# Interfaces.net
KiCad netlist of a schematic drawn in Altium Designer
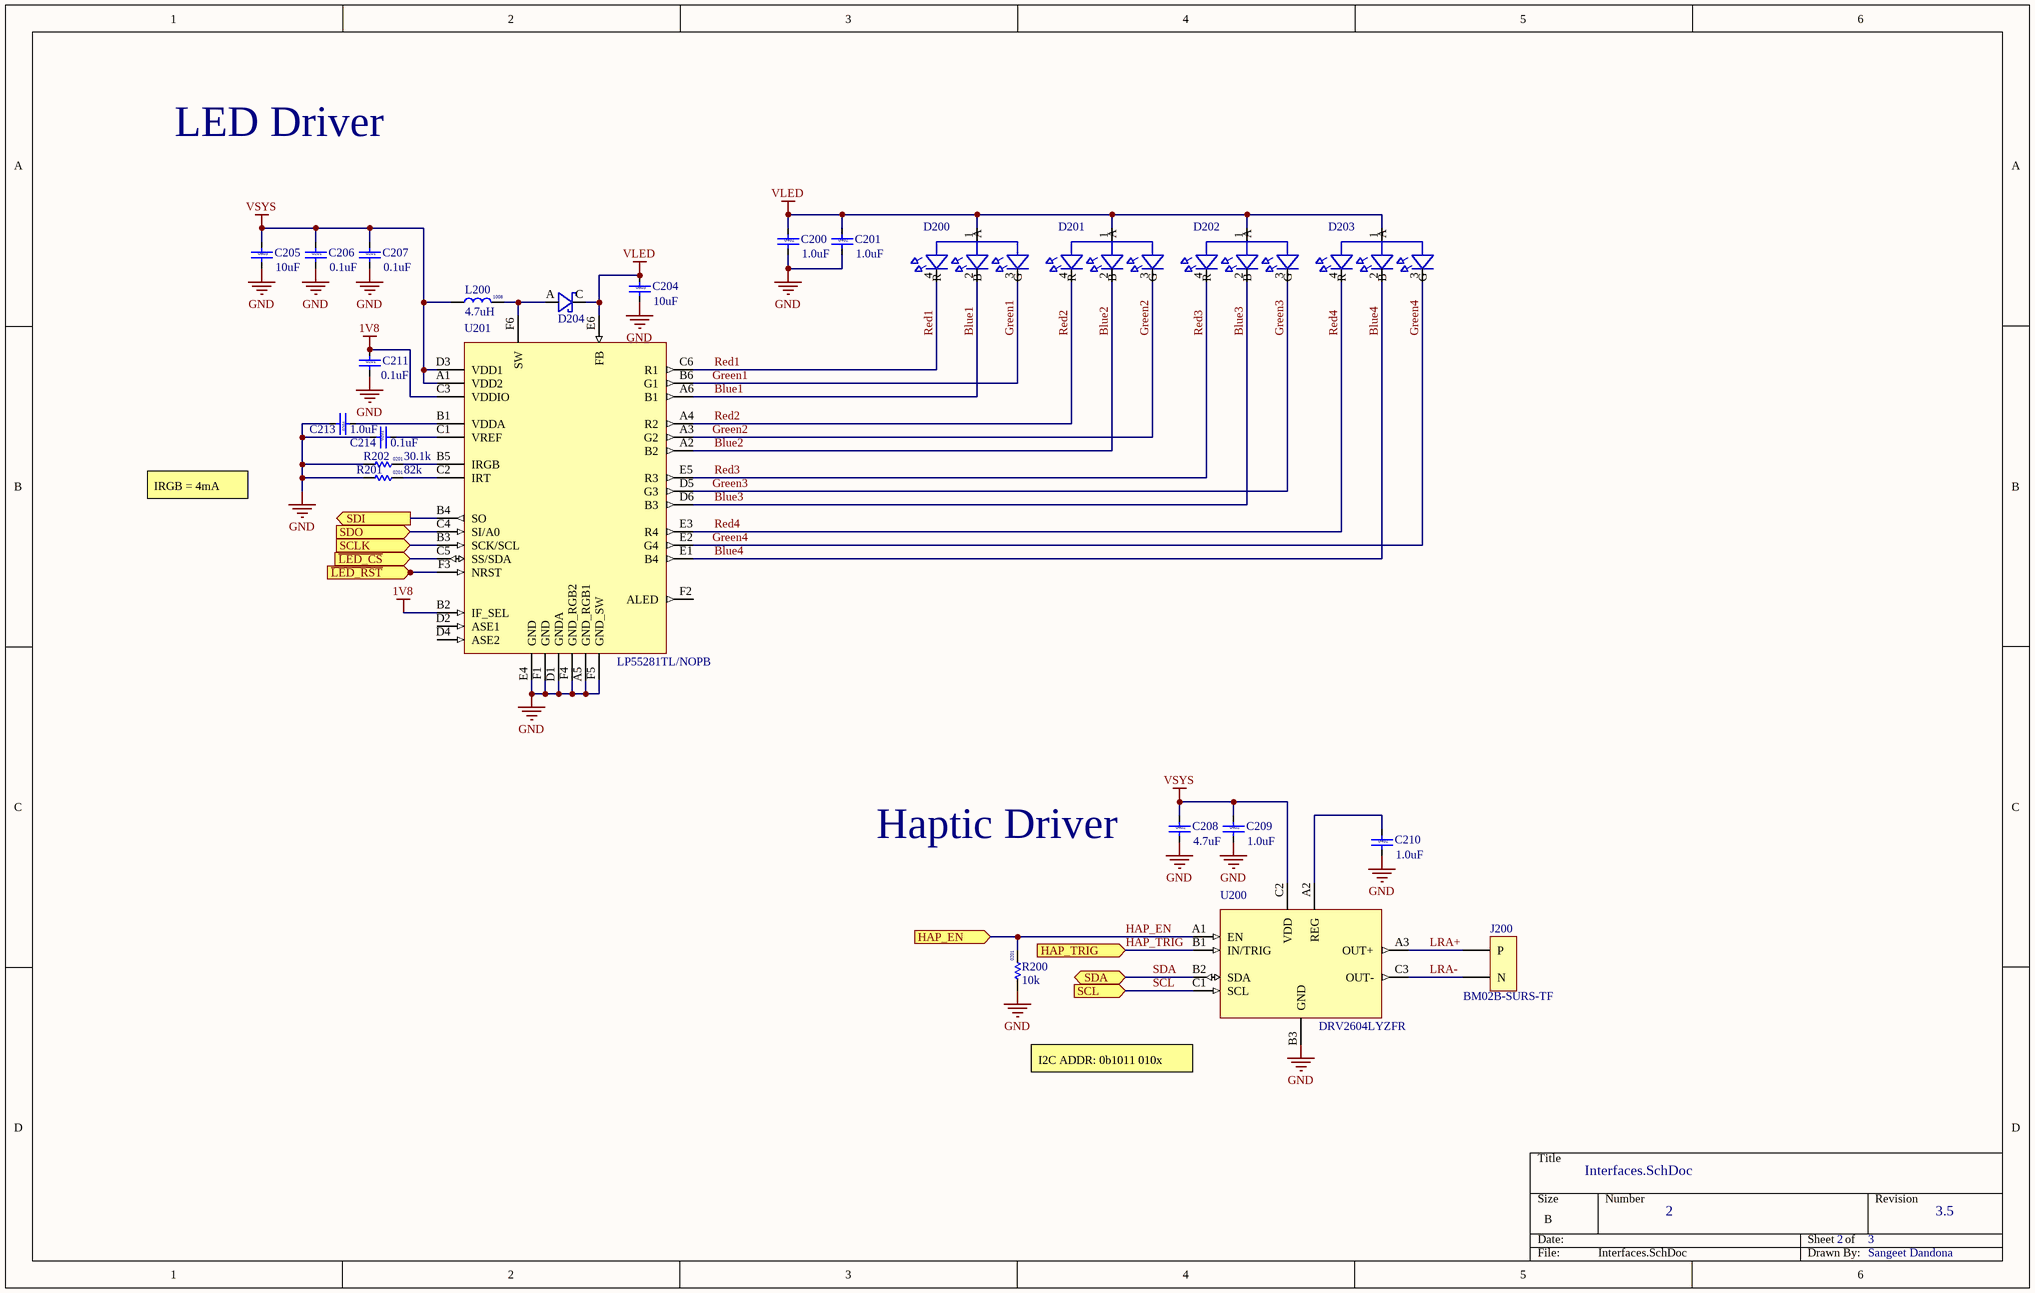
[diagram p0: Interfaces.SchDoc]

(export (version "E")
  (design (tool "Eeschema 10.0.6"))
  (components
    (comp (ref "C200")
      (value "1.0uF")
      (footprint "Cap 0402 HD")
      (description "CAP CER 1UF 10V 10% X5R 0402")
      (fields (field (name "SIZE") "0402") (field (name "MF") "Murata Electronics North America"))
      (libsource (lib "Rigado_AltiumLib") (part "Cap Chip"))
    )
    (comp (ref "C201")
      (value "1.0uF")
      (footprint "Cap 0402 HD")
      (description "CAP CER 1UF 10V 10% X5R 0402")
      (fields (field (name "SIZE") "0402") (field (name "MF") "Murata Electronics North America"))
      (libsource (lib "Rigado_AltiumLib") (part "Cap Chip"))
    )
    (comp (ref "C204")
      (value "10uF")
      (footprint "Cap 0603")
      (description "CAP CER 10UF 10V 20% X5R 0603")
      (fields (field (name "SIZE") "0603") (field (name "MF") "TDK Corporation"))
      (libsource (lib "Rigado_AltiumLib") (part "Cap Chip"))
    )
    (comp (ref "C205")
      (value "10uF")
      (footprint "Cap 0603")
      (description "CAP CER 10UF 10V 20% X5R 0603")
      (fields (field (name "SIZE") "0603") (field (name "MF") "TDK Corporation"))
      (libsource (lib "Rigado_AltiumLib") (part "Cap Chip"))
    )
    (comp (ref "C206")
      (value "0.1uF")
      (footprint "Cap 0201 HD")
      (description "CAP CER 0.1UF 6.3V 10% X5R 0201")
      (fields (field (name "SIZE") "0201") (field (name "MF") "Murata Electronics North America"))
      (libsource (lib "Rigado_AltiumLib") (part "Cap Chip"))
    )
    (comp (ref "C207")
      (value "0.1uF")
      (footprint "Cap 0201 HD")
      (description "CAP CER 0.1UF 6.3V 10% X5R 0201")
      (fields (field (name "SIZE") "0201") (field (name "MF") "Murata Electronics North America"))
      (libsource (lib "Rigado_AltiumLib") (part "Cap Chip"))
    )
    (comp (ref "C208")
      (value "4.7uF")
      (footprint "Cap 0402 HD")
      (description "CAP CER 4.7UF 10V 20% X5R 0402")
      (fields (field (name "SIZE") "0402") (field (name "MF") "Samsung Electro-Mechanics America, Inc."))
      (libsource (lib "Rigado_AltiumLib") (part "Cap Chip"))
    )
    (comp (ref "C209")
      (value "1.0uF")
      (footprint "Cap 0402 HD")
      (description "CAP CER 1UF 10V 10% X5R 0402")
      (fields (field (name "SIZE") "0402") (field (name "MF") "Murata Electronics North America"))
      (libsource (lib "Rigado_AltiumLib") (part "Cap Chip"))
    )
    (comp (ref "C210")
      (value "1.0uF")
      (footprint "Cap 0402 HD")
      (description "CAP CER 1UF 10V 10% X5R 0402")
      (fields (field (name "SIZE") "0402") (field (name "MF") "Murata Electronics North America"))
      (libsource (lib "Rigado_AltiumLib") (part "Cap Chip"))
    )
    (comp (ref "C211")
      (value "0.1uF")
      (footprint "Cap 0201 HD")
      (description "CAP CER 0.1UF 6.3V 10% X5R 0201")
      (fields (field (name "SIZE") "0201") (field (name "MF") "Murata Electronics North America"))
      (libsource (lib "Rigado_AltiumLib") (part "Cap Chip"))
    )
    (comp (ref "C213")
      (value "1.0uF")
      (footprint "Cap 0201 HD")
      (description "CAP CER 1UF 6.3V 20% X5R 0201")
      (fields (field (name "SIZE") "0201") (field (name "MF") "Samsung Electro-Mechanics America, Inc."))
      (libsource (lib "Rigado_AltiumLib") (part "Cap Chip"))
    )
    (comp (ref "C214")
      (value "0.1uF")
      (footprint "Cap 0201 HD")
      (description "CAP CER 0.1UF 6.3V 10% X5R 0201")
      (fields (field (name "SIZE") "0201") (field (name "MF") "Murata Electronics North America"))
      (libsource (lib "Rigado_AltiumLib") (part "Cap Chip"))
    )
    (comp (ref "D200")
      (value "~")
      (footprint "4-PLCC")
      (description "LED RGB 3-IN-1 SMD 4PLCC")
      (fields (field (name "MF") "Cree Inc."))
      (libsource (lib "Rigado_AltiumLib") (part "LED_RGB_CA_2"))
    )
    (comp (ref "D201")
      (value "~")
      (footprint "4-PLCC")
      (description "LED RGB 3-IN-1 SMD 4PLCC")
      (fields (field (name "MF") "Cree Inc."))
      (libsource (lib "Rigado_AltiumLib") (part "LED_RGB_CA_2"))
    )
    (comp (ref "D202")
      (value "~")
      (footprint "4-PLCC")
      (description "LED RGB 3-IN-1 SMD 4PLCC")
      (fields (field (name "MF") "Cree Inc."))
      (libsource (lib "Rigado_AltiumLib") (part "LED_RGB_CA_2"))
    )
    (comp (ref "D203")
      (value "~")
      (footprint "4-PLCC")
      (description "LED RGB 3-IN-1 SMD 4PLCC")
      (fields (field (name "MF") "Cree Inc."))
      (libsource (lib "Rigado_AltiumLib") (part "LED_RGB_CA_2"))
    )
    (comp (ref "D204")
      (value "~")
      (footprint "SOD-123F_U")
      (description "DIODE SCHOTTKY 20V 1A SOD123FL")
      (fields (field (name "MF") "ON Semiconductor"))
      (libsource (lib "LOCAL_Rigado_AltiumLib") (part "Diode_Schottky"))
    )
    (comp (ref "J200")
      (value "BM02B-SURS-TF")
      (footprint "BM02B-SURS-TF")
      (description "CONN HDR SUR TOP 2POS 0.8MM TIN")
      (fields (field (name "MF") "JST Sales America Inc."))
      (libsource (lib "JWB-001_Main") (part "BM02B-SURS-TF"))
    )
    (comp (ref "L200")
      (value "4.7uH")
      (footprint "IND 1008")
      (description "FIXED IND 4.7UH 1A 250 MOHM SMD")
      (fields (field (name "SIZE") "1008") (field (name "MF") "Samsung Electro-Mechanics America, Inc."))
      (libsource (lib "Rigado_AltiumLib") (part "Ind sm"))
    )
    (comp (ref "R200")
      (value "10k")
      (footprint "RES 0201 HD")
      (description "RES SMD 10K OHM 5% 1/20W 0201")
      (fields (field (name "SIZE") "0201") (field (name "MF") "Rohm Semiconductor"))
      (libsource (lib "Rigado_AltiumLib") (part "Res sm"))
    )
    (comp (ref "R201")
      (value "82k")
      (footprint "RES 0201 HD")
      (description "RES SMD 82K OHM 1% 1/20W 0201")
      (fields (field (name "SIZE") "0201") (field (name "MF") "Panasonic Electronic Components"))
      (libsource (lib "Rigado_AltiumLib") (part "Res sm"))
    )
    (comp (ref "R202")
      (value "30.1k")
      (footprint "RES 0201 HD")
      (description "RES SMD 30.1K OHM 1% 1/20W 0201")
      (fields (field (name "SIZE") "0201") (field (name "MF") "Panasonic Electronic Components"))
      (libsource (lib "Rigado_AltiumLib") (part "Res sm"))
    )
    (comp (ref "U200")
      (value "~")
      (footprint "BGA0.5P3x3-9Pin")
      (description "IC ERM/LRA HAPTIC DRIVER 9DSBGA")
      (fields (field (name "MF") "Texas Instruments") (field (name "MFPN") "DRV2604LYZFR"))
      (libsource (lib "Rigado_AltiumLib") (part "DRV2604L"))
    )
    (comp (ref "U201")
      (value "~")
      (footprint "BGA0.5P6x6-36Pin")
      (description "IC LED DRIVER RGLTR DIM 36USMD")
      (fields (field (name "MF") "Texas Instruments") (field (name "MFPN") "LP55281TL/NOPB"))
      (libsource (lib "Rigado_AltiumLib") (part "LP55281"))
    )
  )
  (nets
    (net (code "1") (name "/Blue1") (class "Default")
      (node (ref "D200") (pin "2") (pinfunction "B_2") (pintype "passive"))
      (node (ref "U201") (pin "A6") (pinfunction "B1_A6") (pintype "output"))
    )
    (net (code "2") (name "/Blue2") (class "Default")
      (node (ref "D201") (pin "2") (pinfunction "B_2") (pintype "passive"))
      (node (ref "U201") (pin "A2") (pinfunction "B2_A2") (pintype "output"))
    )
    (net (code "3") (name "/Blue3") (class "Default")
      (node (ref "D202") (pin "2") (pinfunction "B_2") (pintype "passive"))
      (node (ref "U201") (pin "D6") (pinfunction "B3_D6") (pintype "output"))
    )
    (net (code "4") (name "/Blue4") (class "Default")
      (node (ref "D203") (pin "2") (pinfunction "B_2") (pintype "passive"))
      (node (ref "U201") (pin "E1") (pinfunction "B4_E1") (pintype "output"))
    )
    (net (code "5") (name "/Green1") (class "Default")
      (node (ref "D200") (pin "3") (pinfunction "G_3") (pintype "passive"))
      (node (ref "U201") (pin "B6") (pinfunction "G1_B6") (pintype "output"))
    )
    (net (code "6") (name "/Green2") (class "Default")
      (node (ref "D201") (pin "3") (pinfunction "G_3") (pintype "passive"))
      (node (ref "U201") (pin "A3") (pinfunction "G2_A3") (pintype "output"))
    )
    (net (code "7") (name "/Green3") (class "Default")
      (node (ref "D202") (pin "3") (pinfunction "G_3") (pintype "passive"))
      (node (ref "U201") (pin "D5") (pinfunction "G3_D5") (pintype "output"))
    )
    (net (code "8") (name "/Green4") (class "Default")
      (node (ref "D203") (pin "3") (pinfunction "G_3") (pintype "passive"))
      (node (ref "U201") (pin "E2") (pinfunction "G4_E2") (pintype "output"))
    )
    (net (code "9") (name "/HAP_EN") (class "Default")
      (node (ref "R200") (pin "2") (pinfunction "2_2") (pintype "passive"))
      (node (ref "U200") (pin "A1") (pinfunction "EN_A1") (pintype "input"))
    )
    (net (code "10") (name "/HAP_TRIG") (class "Default")
      (node (ref "U200") (pin "B1") (pinfunction "IN/TRIG_B1") (pintype "input"))
    )
    (net (code "11") (name "/LED_CS") (class "Default")
      (node (ref "U201") (pin "C5") (pinfunction "SS/SDA_C5") (pintype "bidirectional"))
    )
    (net (code "12") (name "/LED_RST") (class "Default")
      (node (ref "U201") (pin "F3") (pinfunction "NRST_F3") (pintype "input"))
    )
    (net (code "13") (name "/LRA+") (class "Default")
      (node (ref "J200") (pin "1") (pinfunction "P_1") (pintype "passive"))
      (node (ref "U200") (pin "A3") (pinfunction "OUT+_A3") (pintype "output"))
    )
    (net (code "14") (name "/LRA-") (class "Default")
      (node (ref "J200") (pin "2") (pinfunction "N_2") (pintype "passive"))
      (node (ref "U200") (pin "C3") (pinfunction "OUT-_C3") (pintype "output"))
    )
    (net (code "15") (name "/Red1") (class "Default")
      (node (ref "D200") (pin "4") (pinfunction "R_4") (pintype "passive"))
      (node (ref "U201") (pin "C6") (pinfunction "R1_C6") (pintype "output"))
    )
    (net (code "16") (name "/Red2") (class "Default")
      (node (ref "D201") (pin "4") (pinfunction "R_4") (pintype "passive"))
      (node (ref "U201") (pin "A4") (pinfunction "R2_A4") (pintype "output"))
    )
    (net (code "17") (name "/Red3") (class "Default")
      (node (ref "D202") (pin "4") (pinfunction "R_4") (pintype "passive"))
      (node (ref "U201") (pin "E5") (pinfunction "R3_E5") (pintype "output"))
    )
    (net (code "18") (name "/Red4") (class "Default")
      (node (ref "D203") (pin "4") (pinfunction "R_4") (pintype "passive"))
      (node (ref "U201") (pin "E3") (pinfunction "R4_E3") (pintype "output"))
    )
    (net (code "19") (name "/SCL") (class "Default")
      (node (ref "U200") (pin "C1") (pinfunction "SCL_C1") (pintype "input"))
    )
    (net (code "20") (name "/SCLK") (class "Default")
      (node (ref "U201") (pin "B3") (pinfunction "SCK/SCL_B3") (pintype "input"))
    )
    (net (code "21") (name "/SDA") (class "Default")
      (node (ref "U200") (pin "B2") (pinfunction "SDA_B2") (pintype "bidirectional"))
    )
    (net (code "22") (name "/SDI") (class "Default")
      (node (ref "U201") (pin "B4") (pinfunction "SO_B4") (pintype "output"))
    )
    (net (code "23") (name "/SDO") (class "Default")
      (node (ref "U201") (pin "C4") (pinfunction "SI/A0_C4") (pintype "input"))
    )
    (net (code "24") (name "1V8") (class "Default")
      (node (ref "C211") (pin "1") (pinfunction "1_1") (pintype "passive"))
      (node (ref "U201") (pin "B2") (pinfunction "IF_SEL_B2") (pintype "input"))
      (node (ref "U201") (pin "C3") (pinfunction "VDDIO_C3") (pintype "power_in"))
    )
    (net (code "25") (name "GND") (class "Default")
      (node (ref "C200") (pin "2") (pinfunction "2_2") (pintype "passive"))
      (node (ref "C201") (pin "2") (pinfunction "2_2") (pintype "passive"))
      (node (ref "C204") (pin "2") (pinfunction "2_2") (pintype "passive"))
      (node (ref "C205") (pin "2") (pinfunction "2_2") (pintype "passive"))
      (node (ref "C206") (pin "2") (pinfunction "2_2") (pintype "passive"))
      (node (ref "C207") (pin "2") (pinfunction "2_2") (pintype "passive"))
      (node (ref "C208") (pin "2") (pinfunction "2_2") (pintype "passive"))
      (node (ref "C209") (pin "2") (pinfunction "2_2") (pintype "passive"))
      (node (ref "C210") (pin "2") (pinfunction "2_2") (pintype "passive"))
      (node (ref "C211") (pin "2") (pinfunction "2_2") (pintype "passive"))
      (node (ref "C213") (pin "2") (pinfunction "2_2") (pintype "passive"))
      (node (ref "C214") (pin "1") (pinfunction "1_1") (pintype "passive"))
      (node (ref "R200") (pin "1") (pinfunction "1_1") (pintype "passive"))
      (node (ref "R201") (pin "1") (pinfunction "1_1") (pintype "passive"))
      (node (ref "R202") (pin "1") (pinfunction "1_1") (pintype "passive"))
      (node (ref "U200") (pin "B3") (pinfunction "GND_B3") (pintype "power_in"))
      (node (ref "U201") (pin "A5") (pinfunction "GND_RGB1_A5") (pintype "power_in"))
      (node (ref "U201") (pin "D1") (pinfunction "GNDA_D1") (pintype "power_in"))
      (node (ref "U201") (pin "E4") (pinfunction "GND_E4") (pintype "power_in"))
      (node (ref "U201") (pin "F1") (pinfunction "GND_F1") (pintype "power_in"))
      (node (ref "U201") (pin "F4") (pinfunction "GND_RGB2_F4") (pintype "power_in"))
      (node (ref "U201") (pin "F5") (pinfunction "GND_SW_F5") (pintype "power_in"))
    )
    (net (code "26") (name "Net-(U200-REG)") (class "Default")
      (node (ref "C210") (pin "1") (pinfunction "1_1") (pintype "passive"))
      (node (ref "U200") (pin "A2") (pinfunction "REG_A2") (pintype "power_in"))
    )
    (net (code "27") (name "Net-(U201-IRGB)") (class "Default")
      (node (ref "R202") (pin "2") (pinfunction "2_2") (pintype "passive"))
      (node (ref "U201") (pin "B5") (pinfunction "IRGB_B5") (pintype "passive"))
    )
    (net (code "28") (name "Net-(U201-IRT)") (class "Default")
      (node (ref "R201") (pin "2") (pinfunction "2_2") (pintype "passive"))
      (node (ref "U201") (pin "C2") (pinfunction "IRT_C2") (pintype "passive"))
    )
    (net (code "29") (name "Net-(U201-SW)") (class "Default")
      (node (ref "D204") (pin "A") (pintype "passive"))
      (node (ref "L200") (pin "2") (pinfunction "2_2") (pintype "passive"))
      (node (ref "U201") (pin "F6") (pinfunction "SW_F6") (pintype "power_in"))
    )
    (net (code "30") (name "Net-(U201-VDDA)") (class "Default")
      (node (ref "C213") (pin "1") (pinfunction "1_1") (pintype "passive"))
      (node (ref "U201") (pin "B1") (pinfunction "VDDA_B1") (pintype "power_in"))
    )
    (net (code "31") (name "Net-(U201-VREF)") (class "Default")
      (node (ref "C214") (pin "2") (pinfunction "2_2") (pintype "passive"))
      (node (ref "U201") (pin "C1") (pinfunction "VREF_C1") (pintype "passive"))
    )
    (net (code "32") (name "VLED") (class "Default")
      (node (ref "C200") (pin "1") (pinfunction "1_1") (pintype "passive"))
      (node (ref "C201") (pin "1") (pinfunction "1_1") (pintype "passive"))
      (node (ref "C204") (pin "1") (pinfunction "1_1") (pintype "passive"))
      (node (ref "D200") (pin "1") (pinfunction "A_1") (pintype "passive"))
      (node (ref "D201") (pin "1") (pinfunction "A_1") (pintype "passive"))
      (node (ref "D202") (pin "1") (pinfunction "A_1") (pintype "passive"))
      (node (ref "D203") (pin "1") (pinfunction "A_1") (pintype "passive"))
      (node (ref "D204") (pin "C") (pintype "passive"))
      (node (ref "U201") (pin "E6") (pinfunction "FB_E6") (pintype "input"))
    )
    (net (code "33") (name "VSYS") (class "Default")
      (node (ref "C205") (pin "1") (pinfunction "1_1") (pintype "passive"))
      (node (ref "C206") (pin "1") (pinfunction "1_1") (pintype "passive"))
      (node (ref "C207") (pin "1") (pinfunction "1_1") (pintype "passive"))
      (node (ref "C208") (pin "1") (pinfunction "1_1") (pintype "passive"))
      (node (ref "C209") (pin "1") (pinfunction "1_1") (pintype "passive"))
      (node (ref "L200") (pin "1") (pinfunction "1_1") (pintype "passive"))
      (node (ref "U200") (pin "C2") (pinfunction "VDD_C2") (pintype "power_in"))
      (node (ref "U201") (pin "A1") (pinfunction "VDD2_A1") (pintype "power_in"))
      (node (ref "U201") (pin "D3") (pinfunction "VDD1_D3") (pintype "power_in"))
    )
    (net (code "34") (name "unconnected-(U201-ALED-PadF2)") (class "Default")
      (node (ref "U201") (pin "F2") (pinfunction "ALED_F2") (pintype "output"))
    )
    (net (code "35") (name "unconnected-(U201-ASE1-PadD2)") (class "Default")
      (node (ref "U201") (pin "D2") (pinfunction "ASE1_D2") (pintype "input"))
    )
    (net (code "36") (name "unconnected-(U201-ASE2-PadD4)") (class "Default")
      (node (ref "U201") (pin "D4") (pinfunction "ASE2_D4") (pintype "input"))
    )
  )
)
